# Sheet.net
KiCad netlist of a schematic drawn in EasyEDA
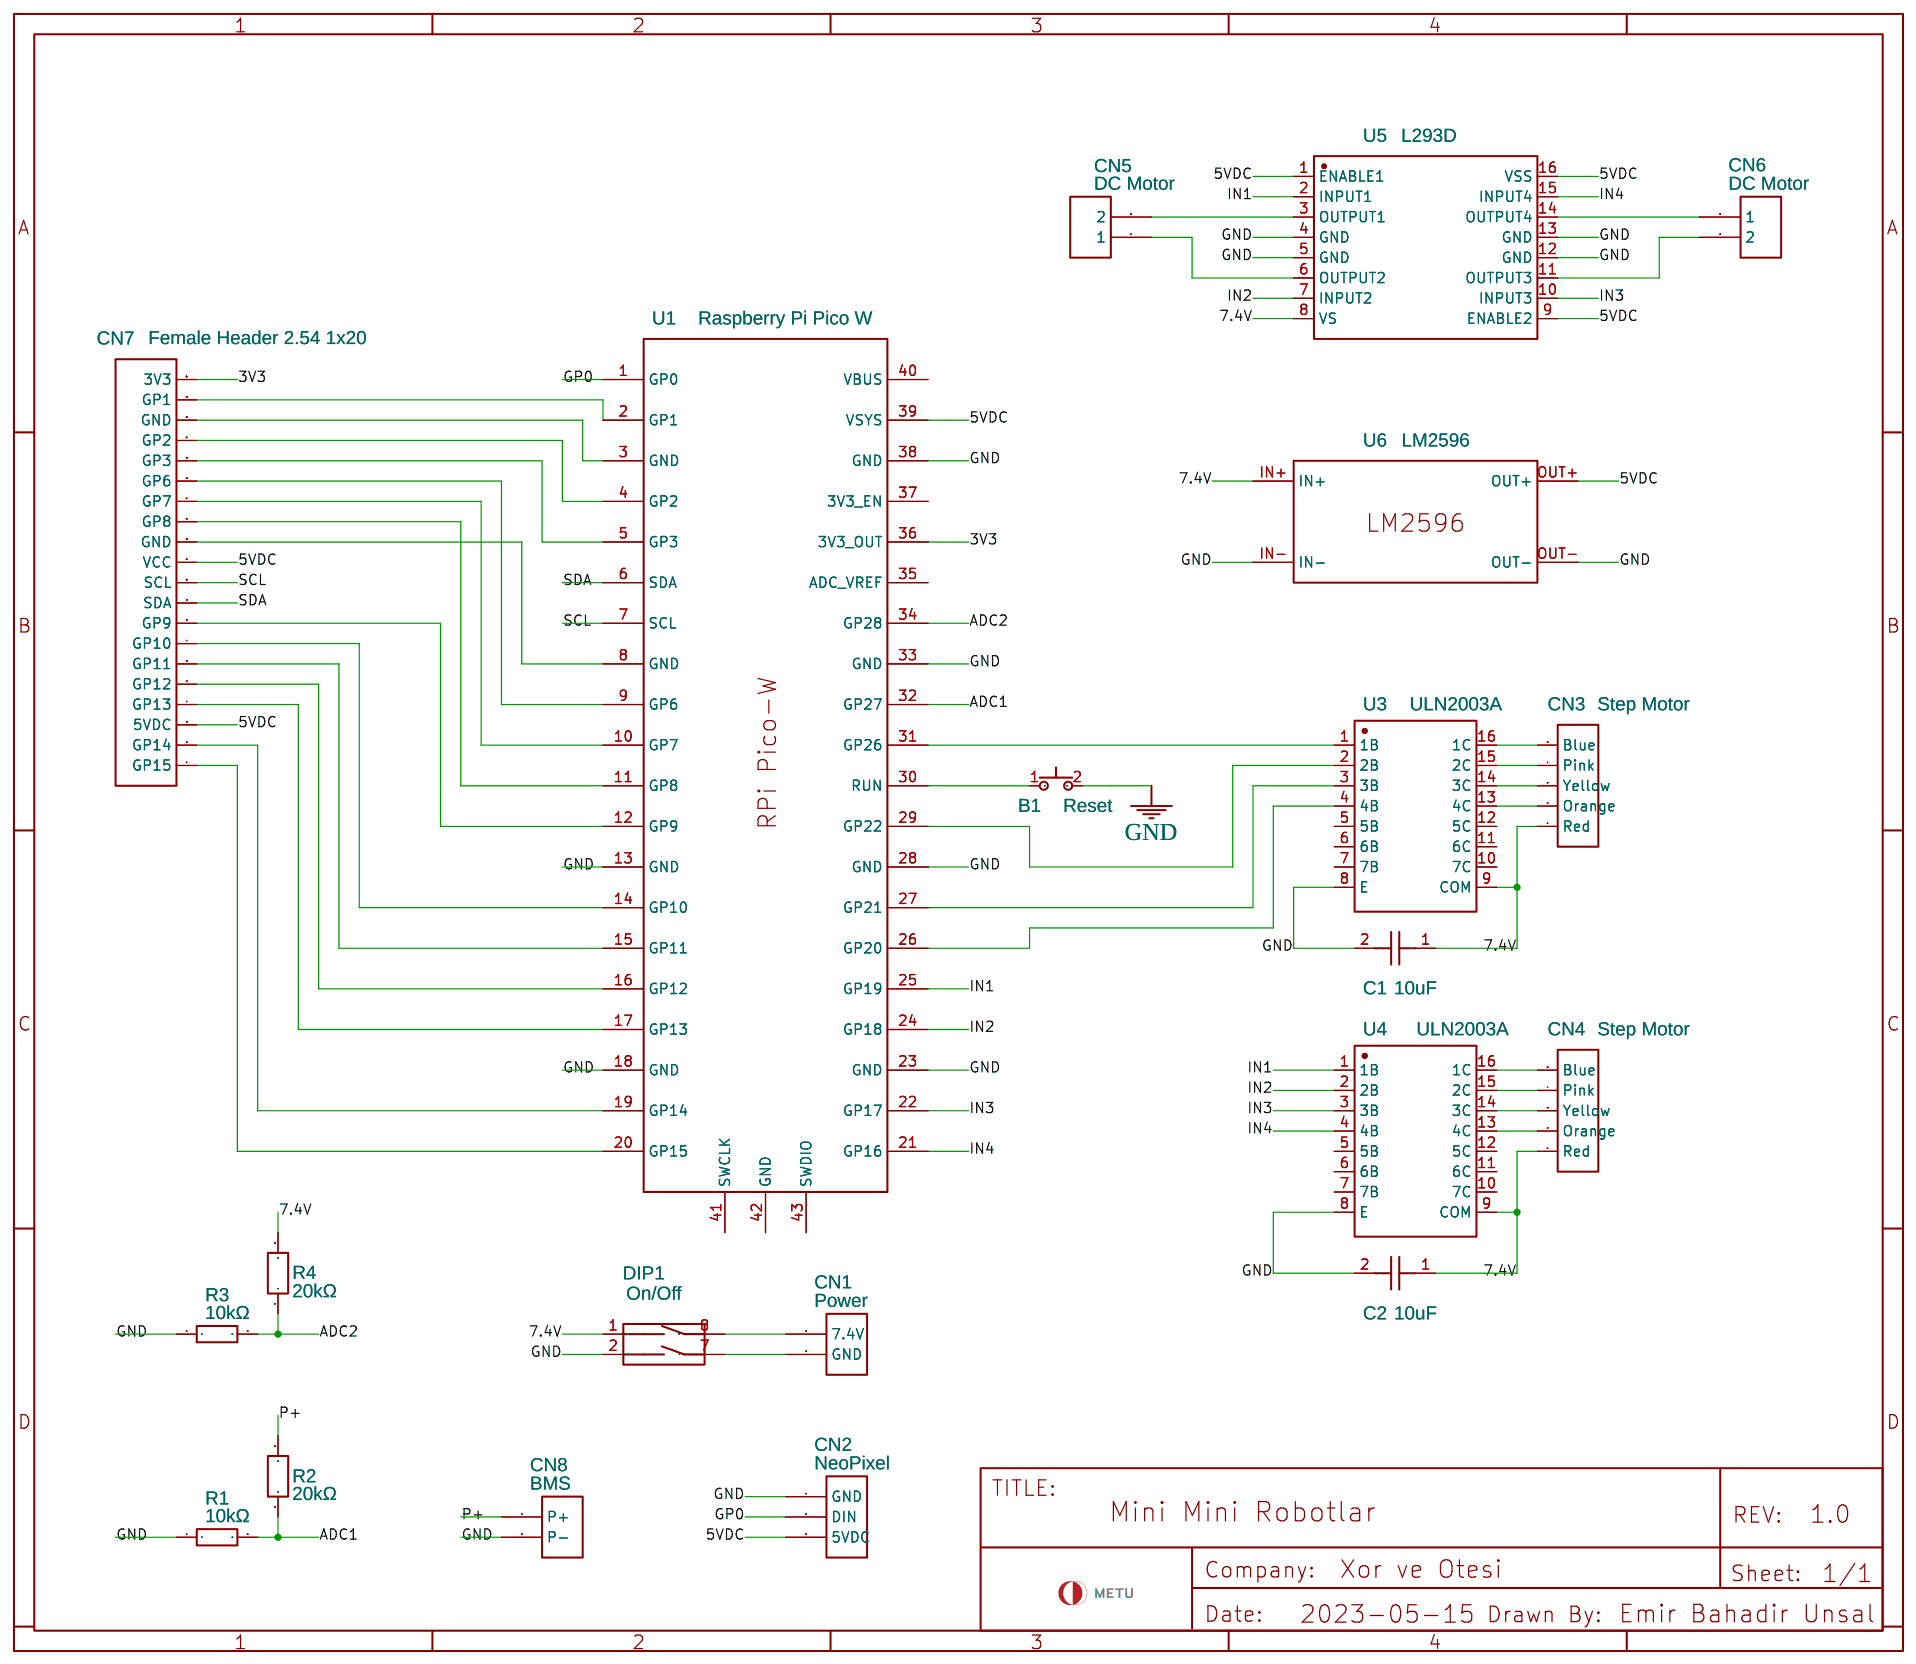
[diagram p0: schematic sheet]

(export (version "E")
  (design (tool "Eeschema 10.0.6"))
  (components
    (comp (ref "B1") (value "Reset") (libsource (lib "") (part "button")))
    (comp (ref "C1")
      (value "10uF")
      (fields
        (field (name "BOM_Manufacturer Part") "FG26X7R1E106KRT00")
        (field (name "BOM_Supplier Part") "C3695070")
      )
      (libsource (lib "") (part "FG26X7R1E106KRT00"))
    )
    (comp (ref "C2")
      (value "10uF")
      (fields
        (field (name "BOM_Manufacturer Part") "FG26X7R1E106KRT00")
        (field (name "BOM_Supplier Part") "C3695070")
      )
      (libsource (lib "") (part "FG26X7R1E106KRT00"))
    )
    (comp (ref "CN1")
      (value "Power")
      (fields (field (name "BOM_Manufacturer Part") "JST"))
      (libsource (lib "") (part "JST-XH_2P_2.54MM"))
    )
    (comp (ref "CN2")
      (value "NeoPixel")
      (fields (field (name "BOM_Manufacturer Part") "JST"))
      (libsource (lib "") (part "JST-XH_3P_2.54MM"))
    )
    (comp (ref "CN3") (value "Step Motor") (libsource (lib "") (part "JST 2.54mm 5pin")))
    (comp (ref "CN4") (value "Step Motor") (libsource (lib "") (part "JST 2.54mm 5pin")))
    (comp (ref "CN5")
      (value "DC Motor")
      (fields (field (name "BOM_Manufacturer Part") "JST"))
      (libsource (lib "") (part "JST-XH_2P_2.54MM_3"))
    )
    (comp (ref "CN6")
      (value "DC Motor")
      (fields (field (name "BOM_Manufacturer Part") "JST"))
      (libsource (lib "") (part "JST-XH_2P_2.54MM_2"))
    )
    (comp (ref "CN7")
      (value "Female Header 2.54 1x20")
      (fields
        (field (name "BOM_Manufacturer Part") "2.54-1*20P母")
        (field (name "BOM_Supplier Part") "C50984")
      )
      (libsource (lib "") (part "Header-Female-2.54_1x20"))
    )
    (comp (ref "CN8")
      (value "BMS")
      (fields (field (name "BOM_Manufacturer Part") "JST"))
      (libsource (lib "") (part "JST-XH_2P_2.54MM_1"))
    )
    (comp (ref "DIP1")
      (value "On/Off")
      (fields
        (field (name "BOM_Manufacturer Part") "DIP switchEI-08")
        (field (name "BOM_Supplier Part") "C90019")
      )
      (libsource (lib "") (part "DIP SWITCH 2"))
    )
    (comp (ref "R1")
      (value "10kΩ")
      (fields
        (field (name "BOM_Manufacturer Part") "RI40-1/4W-10KΩ ±5% T")
        (field (name "BOM_Supplier Part") "C136549")
      )
      (libsource (lib "") (part "RI40-1/4W-10KΩ ±5% T"))
    )
    (comp (ref "R2")
      (value "20kΩ")
      (fields
        (field (name "BOM_Manufacturer Part") "MF1/4W-20KΩ±1%T52")
        (field (name "BOM_Supplier Part") "C714021")
      )
      (libsource (lib "") (part "MF1/4W-20KΩ±1%T52"))
    )
    (comp (ref "R3")
      (value "10kΩ")
      (fields
        (field (name "BOM_Manufacturer Part") "RI40-1/4W-10KΩ ±5% T")
        (field (name "BOM_Supplier Part") "C136549")
      )
      (libsource (lib "") (part "RI40-1/4W-10KΩ ±5% T"))
    )
    (comp (ref "R4")
      (value "20kΩ")
      (fields
        (field (name "BOM_Manufacturer Part") "MF1/4W-20KΩ±1%T52")
        (field (name "BOM_Supplier Part") "C714021")
      )
      (libsource (lib "") (part "MF1/4W-20KΩ±1%T52"))
    )
    (comp (ref "U1")
      (value "Raspberry Pi Pico W")
      (fields
        (field (name "BOM_Manufacturer Part") "Pi Pico")
        (field (name "BOM_Supplier Part") "Raspberry Pi Pico-W")
      )
      (libsource (lib "") (part "RPi Pico-W"))
    )
    (comp (ref "U3")
      (value "ULN2003A")
      (fields (field (name "BOM_Manufacturer Part") "ULN2003APG") (field (name "BOM_Supplier Part") "C5251"))
      (libsource (lib "") (part "ULN2003APG"))
    )
    (comp (ref "U4")
      (value "ULN2003A")
      (fields (field (name "BOM_Manufacturer Part") "ULN2003APG") (field (name "BOM_Supplier Part") "C5251"))
      (libsource (lib "") (part "ULN2003APG"))
    )
    (comp (ref "U5")
      (value "L293D")
      (fields (field (name "BOM_Manufacturer Part") "L293DN") (field (name "BOM_Supplier Part") "C434590"))
      (libsource (lib "") (part "L293DN"))
    )
    (comp (ref "U6") (value "LM2596") (libsource (lib "") (part "LM2596")))
  )
  (nets
    (net (code "1") (name "/3V3") (class "Default")
      (node (ref "CN7") (pin "20") (pinfunction "3V3_20") (pintype "input"))
      (node (ref "U1") (pin "36") (pinfunction "3V3_OUT_36") (pintype "unspecified"))
    )
    (net (code "2") (name "/5VDC") (class "Default")
      (node (ref "CN2") (pin "3") (pinfunction "5VDC_3") (pintype "unspecified"))
      (node (ref "CN7") (pin "11") (pinfunction "VCC_11") (pintype "input"))
      (node (ref "CN7") (pin "3") (pinfunction "5VDC_3") (pintype "input"))
      (node (ref "U1") (pin "39") (pinfunction "VSYS_39") (pintype "unspecified"))
      (node (ref "U5") (pin "1") (pinfunction "ENABLE1_1") (pintype "unspecified"))
      (node (ref "U5") (pin "16") (pinfunction "VSS_16") (pintype "unspecified"))
      (node (ref "U5") (pin "9") (pinfunction "ENABLE2_9") (pintype "unspecified"))
      (node (ref "U6") (pin "OUT+") (pinfunction "OUT+_OUT+") (pintype "unspecified"))
    )
    (net (code "3") (name "/7.4V") (class "Default")
      (node (ref "C1") (pin "1") (pinfunction "1_1") (pintype "unspecified"))
      (node (ref "C2") (pin "1") (pinfunction "1_1") (pintype "unspecified"))
      (node (ref "CN3") (pin "1") (pinfunction "Red_1") (pintype "unspecified"))
      (node (ref "CN4") (pin "1") (pinfunction "Red_1") (pintype "unspecified"))
      (node (ref "DIP1") (pin "1") (pinfunction "1_1") (pintype "unspecified"))
      (node (ref "R4") (pin "2") (pinfunction "2_2") (pintype "unspecified"))
      (node (ref "U3") (pin "9") (pinfunction "COM_9") (pintype "unspecified"))
      (node (ref "U4") (pin "9") (pinfunction "COM_9") (pintype "unspecified"))
      (node (ref "U5") (pin "8") (pinfunction "VS_8") (pintype "unspecified"))
      (node (ref "U6") (pin "IN+") (pinfunction "IN+_IN+") (pintype "unspecified"))
    )
    (net (code "4") (name "/ADC1") (class "Default")
      (node (ref "R1") (pin "2") (pinfunction "2_2") (pintype "unspecified"))
      (node (ref "R2") (pin "1") (pinfunction "1_1") (pintype "unspecified"))
      (node (ref "U1") (pin "32") (pinfunction "GP27_32") (pintype "unspecified"))
    )
    (net (code "5") (name "/ADC2") (class "Default")
      (node (ref "R3") (pin "2") (pinfunction "2_2") (pintype "unspecified"))
      (node (ref "R4") (pin "1") (pinfunction "1_1") (pintype "unspecified"))
      (node (ref "U1") (pin "34") (pinfunction "GP28_34") (pintype "unspecified"))
    )
    (net (code "6") (name "/GP0") (class "Default")
      (node (ref "CN2") (pin "2") (pinfunction "DIN_2") (pintype "unspecified"))
      (node (ref "U1") (pin "1") (pinfunction "GP0_1") (pintype "unspecified"))
    )
    (net (code "7") (name "/IN1") (class "Default")
      (node (ref "U1") (pin "25") (pinfunction "GP19_25") (pintype "unspecified"))
      (node (ref "U4") (pin "1") (pinfunction "1B_1") (pintype "unspecified"))
      (node (ref "U5") (pin "2") (pinfunction "INPUT1_2") (pintype "unspecified"))
    )
    (net (code "8") (name "/IN2") (class "Default")
      (node (ref "U1") (pin "24") (pinfunction "GP18_24") (pintype "unspecified"))
      (node (ref "U4") (pin "2") (pinfunction "2B_2") (pintype "unspecified"))
      (node (ref "U5") (pin "7") (pinfunction "INPUT2_7") (pintype "unspecified"))
    )
    (net (code "9") (name "/IN3") (class "Default")
      (node (ref "U1") (pin "22") (pinfunction "GP17_22") (pintype "unspecified"))
      (node (ref "U4") (pin "3") (pinfunction "3B_3") (pintype "unspecified"))
      (node (ref "U5") (pin "10") (pinfunction "INPUT3_10") (pintype "unspecified"))
    )
    (net (code "10") (name "/IN4") (class "Default")
      (node (ref "U1") (pin "21") (pinfunction "GP16_21") (pintype "unspecified"))
      (node (ref "U4") (pin "4") (pinfunction "4B_4") (pintype "unspecified"))
      (node (ref "U5") (pin "15") (pinfunction "INPUT4_15") (pintype "unspecified"))
    )
    (net (code "11") (name "/P+") (class "Default")
      (node (ref "CN8") (pin "1") (pinfunction "P+_1") (pintype "unspecified"))
      (node (ref "R2") (pin "2") (pinfunction "2_2") (pintype "unspecified"))
    )
    (net (code "12") (name "/SCL") (class "Default")
      (node (ref "CN7") (pin "10") (pinfunction "SCL_10") (pintype "input"))
      (node (ref "U1") (pin "7") (pinfunction "SCL_7") (pintype "unspecified"))
    )
    (net (code "13") (name "/SDA") (class "Default")
      (node (ref "CN7") (pin "9") (pinfunction "SDA_9") (pintype "input"))
      (node (ref "U1") (pin "6") (pinfunction "SDA_6") (pintype "unspecified"))
    )
    (net (code "14") (name "GND") (class "Default")
      (node (ref "B1") (pin "2") (pinfunction "2_2") (pintype "unspecified"))
      (node (ref "C1") (pin "2") (pinfunction "2_2") (pintype "unspecified"))
      (node (ref "C2") (pin "2") (pinfunction "2_2") (pintype "unspecified"))
      (node (ref "CN2") (pin "1") (pinfunction "GND_1") (pintype "unspecified"))
      (node (ref "CN8") (pin "2") (pinfunction "P-_2") (pintype "unspecified"))
      (node (ref "DIP1") (pin "2") (pinfunction "2_2") (pintype "unspecified"))
      (node (ref "R1") (pin "1") (pinfunction "1_1") (pintype "unspecified"))
      (node (ref "R3") (pin "1") (pinfunction "1_1") (pintype "unspecified"))
      (node (ref "U1") (pin "13") (pinfunction "GND_13") (pintype "unspecified"))
      (node (ref "U1") (pin "18") (pinfunction "GND_18") (pintype "unspecified"))
      (node (ref "U1") (pin "23") (pinfunction "GND_23") (pintype "unspecified"))
      (node (ref "U1") (pin "28") (pinfunction "GND_28") (pintype "unspecified"))
      (node (ref "U1") (pin "33") (pinfunction "GND_33") (pintype "unspecified"))
      (node (ref "U1") (pin "38") (pinfunction "GND_38") (pintype "unspecified"))
      (node (ref "U3") (pin "8") (pinfunction "E_8") (pintype "unspecified"))
      (node (ref "U4") (pin "8") (pinfunction "E_8") (pintype "unspecified"))
      (node (ref "U5") (pin "12") (pinfunction "GND_12") (pintype "unspecified"))
      (node (ref "U5") (pin "13") (pinfunction "GND_13") (pintype "unspecified"))
      (node (ref "U5") (pin "4") (pinfunction "GND_4") (pintype "unspecified"))
      (node (ref "U5") (pin "5") (pinfunction "GND_5") (pintype "unspecified"))
      (node (ref "U6") (pin "IN-") (pinfunction "IN-_IN-") (pintype "unspecified"))
      (node (ref "U6") (pin "OUT-") (pinfunction "OUT-_OUT-") (pintype "unspecified"))
    )
    (net (code "15") (name "Net-(CN1-7.4V)") (class "Default")
      (node (ref "CN1") (pin "1") (pinfunction "7.4V_1") (pintype "unspecified"))
      (node (ref "DIP1") (pin "8") (pinfunction "8_8") (pintype "unspecified"))
    )
    (net (code "16") (name "Net-(CN1-GND)") (class "Default")
      (node (ref "CN1") (pin "2") (pinfunction "GND_2") (pintype "unspecified"))
      (node (ref "DIP1") (pin "7") (pinfunction "7_7") (pintype "unspecified"))
    )
    (net (code "17") (name "Net-(CN3-Blue)") (class "Default")
      (node (ref "CN3") (pin "5") (pinfunction "Blue_5") (pintype "unspecified"))
      (node (ref "U3") (pin "16") (pinfunction "1C_16") (pintype "unspecified"))
    )
    (net (code "18") (name "Net-(CN3-Orange)") (class "Default")
      (node (ref "CN3") (pin "2") (pinfunction "Orange_2") (pintype "unspecified"))
      (node (ref "U3") (pin "13") (pinfunction "4C_13") (pintype "unspecified"))
    )
    (net (code "19") (name "Net-(CN3-Pink)") (class "Default")
      (node (ref "CN3") (pin "4") (pinfunction "Pink_4") (pintype "unspecified"))
      (node (ref "U3") (pin "15") (pinfunction "2C_15") (pintype "unspecified"))
    )
    (net (code "20") (name "Net-(CN3-Yellow)") (class "Default")
      (node (ref "CN3") (pin "3") (pinfunction "Yellow_3") (pintype "unspecified"))
      (node (ref "U3") (pin "14") (pinfunction "3C_14") (pintype "unspecified"))
    )
    (net (code "21") (name "Net-(CN4-Blue)") (class "Default")
      (node (ref "CN4") (pin "5") (pinfunction "Blue_5") (pintype "unspecified"))
      (node (ref "U4") (pin "16") (pinfunction "1C_16") (pintype "unspecified"))
    )
    (net (code "22") (name "Net-(CN4-Orange)") (class "Default")
      (node (ref "CN4") (pin "2") (pinfunction "Orange_2") (pintype "unspecified"))
      (node (ref "U4") (pin "13") (pinfunction "4C_13") (pintype "unspecified"))
    )
    (net (code "23") (name "Net-(CN4-Pink)") (class "Default")
      (node (ref "CN4") (pin "4") (pinfunction "Pink_4") (pintype "unspecified"))
      (node (ref "U4") (pin "15") (pinfunction "2C_15") (pintype "unspecified"))
    )
    (net (code "24") (name "Net-(CN4-Yellow)") (class "Default")
      (node (ref "CN4") (pin "3") (pinfunction "Yellow_3") (pintype "unspecified"))
      (node (ref "U4") (pin "14") (pinfunction "3C_14") (pintype "unspecified"))
    )
    (net (code "25") (name "Net-(CN7-GND-Pad12)") (class "Default")
      (node (ref "CN7") (pin "12") (pinfunction "GND_12") (pintype "input"))
      (node (ref "U1") (pin "8") (pinfunction "GND_8") (pintype "unspecified"))
    )
    (net (code "26") (name "Net-(CN7-GND-Pad18)") (class "Default")
      (node (ref "CN7") (pin "18") (pinfunction "GND_18") (pintype "input"))
      (node (ref "U1") (pin "3") (pinfunction "GND_3") (pintype "unspecified"))
    )
    (net (code "27") (name "Net-(CN7-GP1)") (class "Default")
      (node (ref "CN7") (pin "19") (pinfunction "GP1_19") (pintype "input"))
      (node (ref "U1") (pin "2") (pinfunction "GP1_2") (pintype "unspecified"))
    )
    (net (code "28") (name "Net-(CN7-GP2)") (class "Default")
      (node (ref "CN7") (pin "17") (pinfunction "GP2_17") (pintype "input"))
      (node (ref "U1") (pin "4") (pinfunction "GP2_4") (pintype "unspecified"))
    )
    (net (code "29") (name "Net-(CN7-GP3)") (class "Default")
      (node (ref "CN7") (pin "16") (pinfunction "GP3_16") (pintype "input"))
      (node (ref "U1") (pin "5") (pinfunction "GP3_5") (pintype "unspecified"))
    )
    (net (code "30") (name "Net-(CN7-GP6)") (class "Default")
      (node (ref "CN7") (pin "15") (pinfunction "GP6_15") (pintype "input"))
      (node (ref "U1") (pin "9") (pinfunction "GP6_9") (pintype "unspecified"))
    )
    (net (code "31") (name "Net-(CN7-GP7)") (class "Default")
      (node (ref "CN7") (pin "14") (pinfunction "GP7_14") (pintype "input"))
      (node (ref "U1") (pin "10") (pinfunction "GP7_10") (pintype "unspecified"))
    )
    (net (code "32") (name "Net-(CN7-GP8)") (class "Default")
      (node (ref "CN7") (pin "13") (pinfunction "GP8_13") (pintype "input"))
      (node (ref "U1") (pin "11") (pinfunction "GP8_11") (pintype "unspecified"))
    )
    (net (code "33") (name "Net-(CN7-GP9)") (class "Default")
      (node (ref "CN7") (pin "8") (pinfunction "GP9_8") (pintype "input"))
      (node (ref "U1") (pin "12") (pinfunction "GP9_12") (pintype "unspecified"))
    )
    (net (code "34") (name "Net-(CN7-GP10)") (class "Default")
      (node (ref "CN7") (pin "7") (pinfunction "GP10_7") (pintype "input"))
      (node (ref "U1") (pin "14") (pinfunction "GP10_14") (pintype "unspecified"))
    )
    (net (code "35") (name "Net-(CN7-GP11)") (class "Default")
      (node (ref "CN7") (pin "6") (pinfunction "GP11_6") (pintype "input"))
      (node (ref "U1") (pin "15") (pinfunction "GP11_15") (pintype "unspecified"))
    )
    (net (code "36") (name "Net-(CN7-GP12)") (class "Default")
      (node (ref "CN7") (pin "5") (pinfunction "GP12_5") (pintype "input"))
      (node (ref "U1") (pin "16") (pinfunction "GP12_16") (pintype "unspecified"))
    )
    (net (code "37") (name "Net-(CN7-GP13)") (class "Default")
      (node (ref "CN7") (pin "4") (pinfunction "GP13_4") (pintype "input"))
      (node (ref "U1") (pin "17") (pinfunction "GP13_17") (pintype "unspecified"))
    )
    (net (code "38") (name "Net-(CN7-GP14)") (class "Default")
      (node (ref "CN7") (pin "2") (pinfunction "GP14_2") (pintype "input"))
      (node (ref "U1") (pin "19") (pinfunction "GP14_19") (pintype "unspecified"))
    )
    (net (code "39") (name "Net-(CN7-GP15)") (class "Default")
      (node (ref "CN7") (pin "1") (pinfunction "GP15_1") (pintype "input"))
      (node (ref "U1") (pin "20") (pinfunction "GP15_20") (pintype "unspecified"))
    )
    (net (code "40") (name "Net-(U1-GP20)") (class "Default")
      (node (ref "U1") (pin "26") (pinfunction "GP20_26") (pintype "unspecified"))
      (node (ref "U3") (pin "4") (pinfunction "4B_4") (pintype "unspecified"))
    )
    (net (code "41") (name "Net-(U1-GP21)") (class "Default")
      (node (ref "U1") (pin "27") (pinfunction "GP21_27") (pintype "unspecified"))
      (node (ref "U3") (pin "3") (pinfunction "3B_3") (pintype "unspecified"))
    )
    (net (code "42") (name "Net-(U1-GP22)") (class "Default")
      (node (ref "U1") (pin "29") (pinfunction "GP22_29") (pintype "unspecified"))
      (node (ref "U3") (pin "2") (pinfunction "2B_2") (pintype "unspecified"))
    )
    (net (code "43") (name "Net-(U1-GP26)") (class "Default")
      (node (ref "U1") (pin "31") (pinfunction "GP26_31") (pintype "unspecified"))
      (node (ref "U3") (pin "1") (pinfunction "1B_1") (pintype "unspecified"))
    )
    (net (code "44") (name "Net-(U1-RUN)") (class "Default")
      (node (ref "B1") (pin "1") (pinfunction "1_1") (pintype "unspecified"))
      (node (ref "U1") (pin "30") (pinfunction "RUN_30") (pintype "unspecified"))
    )
    (net (code "45") (name "Net-(U5-OUTPUT1)") (class "Default")
      (node (ref "CN5") (pin "2") (pinfunction "2_2") (pintype "unspecified"))
      (node (ref "U5") (pin "3") (pinfunction "OUTPUT1_3") (pintype "unspecified"))
    )
    (net (code "46") (name "Net-(U5-OUTPUT2)") (class "Default")
      (node (ref "CN5") (pin "1") (pinfunction "1_1") (pintype "unspecified"))
      (node (ref "U5") (pin "6") (pinfunction "OUTPUT2_6") (pintype "unspecified"))
    )
    (net (code "47") (name "Net-(U5-OUTPUT3)") (class "Default")
      (node (ref "CN6") (pin "2") (pinfunction "2_2") (pintype "unspecified"))
      (node (ref "U5") (pin "11") (pinfunction "OUTPUT3_11") (pintype "unspecified"))
    )
    (net (code "48") (name "Net-(U5-OUTPUT4)") (class "Default")
      (node (ref "CN6") (pin "1") (pinfunction "1_1") (pintype "unspecified"))
      (node (ref "U5") (pin "14") (pinfunction "OUTPUT4_14") (pintype "unspecified"))
    )
    (net (code "49") (name "unconnected-(U1-3V3_EN-Pad37)") (class "Default")
      (node (ref "U1") (pin "37") (pinfunction "3V3_EN_37") (pintype "unspecified"))
    )
    (net (code "50") (name "unconnected-(U1-ADC_VREF-Pad35)") (class "Default")
      (node (ref "U1") (pin "35") (pinfunction "ADC_VREF_35") (pintype "unspecified"))
    )
    (net (code "51") (name "unconnected-(U1-GND-Pad42)") (class "Default")
      (node (ref "U1") (pin "42") (pinfunction "GND_42") (pintype "unspecified"))
    )
    (net (code "52") (name "unconnected-(U1-SWCLK-Pad41)") (class "Default")
      (node (ref "U1") (pin "41") (pinfunction "SWCLK_41") (pintype "unspecified"))
    )
    (net (code "53") (name "unconnected-(U1-SWDIO-Pad43)") (class "Default")
      (node (ref "U1") (pin "43") (pinfunction "SWDIO_43") (pintype "unspecified"))
    )
    (net (code "54") (name "unconnected-(U1-VBUS-Pad40)") (class "Default")
      (node (ref "U1") (pin "40") (pinfunction "VBUS_40") (pintype "unspecified"))
    )
    (net (code "55") (name "unconnected-(U3-5B-Pad5)") (class "Default")
      (node (ref "U3") (pin "5") (pinfunction "5B_5") (pintype "unspecified"))
    )
    (net (code "56") (name "unconnected-(U3-5C-Pad12)") (class "Default")
      (node (ref "U3") (pin "12") (pinfunction "5C_12") (pintype "unspecified"))
    )
    (net (code "57") (name "unconnected-(U3-6B-Pad6)") (class "Default")
      (node (ref "U3") (pin "6") (pinfunction "6B_6") (pintype "unspecified"))
    )
    (net (code "58") (name "unconnected-(U3-6C-Pad11)") (class "Default")
      (node (ref "U3") (pin "11") (pinfunction "6C_11") (pintype "unspecified"))
    )
    (net (code "59") (name "unconnected-(U3-7B-Pad7)") (class "Default")
      (node (ref "U3") (pin "7") (pinfunction "7B_7") (pintype "unspecified"))
    )
    (net (code "60") (name "unconnected-(U3-7C-Pad10)") (class "Default")
      (node (ref "U3") (pin "10") (pinfunction "7C_10") (pintype "unspecified"))
    )
    (net (code "61") (name "unconnected-(U4-5B-Pad5)") (class "Default")
      (node (ref "U4") (pin "5") (pinfunction "5B_5") (pintype "unspecified"))
    )
    (net (code "62") (name "unconnected-(U4-5C-Pad12)") (class "Default")
      (node (ref "U4") (pin "12") (pinfunction "5C_12") (pintype "unspecified"))
    )
    (net (code "63") (name "unconnected-(U4-6B-Pad6)") (class "Default")
      (node (ref "U4") (pin "6") (pinfunction "6B_6") (pintype "unspecified"))
    )
    (net (code "64") (name "unconnected-(U4-6C-Pad11)") (class "Default")
      (node (ref "U4") (pin "11") (pinfunction "6C_11") (pintype "unspecified"))
    )
    (net (code "65") (name "unconnected-(U4-7B-Pad7)") (class "Default")
      (node (ref "U4") (pin "7") (pinfunction "7B_7") (pintype "unspecified"))
    )
    (net (code "66") (name "unconnected-(U4-7C-Pad10)") (class "Default")
      (node (ref "U4") (pin "10") (pinfunction "7C_10") (pintype "unspecified"))
    )
  )
)
